# notch.net
KiCad netlist of a schematic drawn in EAGLE
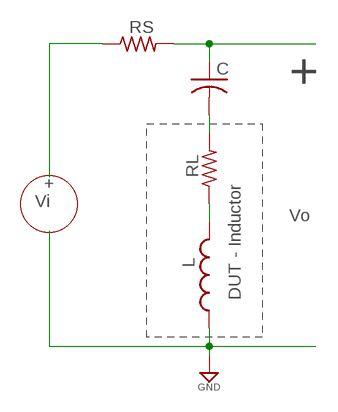
[diagram p0: schematic, sheet 1]

(export (version "E")
  (design (tool "Eeschema 10.0.6"))
  (components
    (comp (ref "C")
      (value "C-US050-030X075")
      (footprint "eagle-import:C050-030X075")
      (libsource (lib "eagle-import") (part "C-US050-030X075"))
    )
    (comp (ref "L")
      (value "L-USL0201")
      (footprint "eagle-import:L0201")
      (libsource (lib "eagle-import") (part "L-USL0201"))
    )
    (comp (ref "RL")
      (value "R-US_0411/15")
      (footprint "eagle-import:0411_15")
      (libsource (lib "eagle-import") (part "R-US_0411/15"))
    )
    (comp (ref "RS")
      (value "R-US_0411/15")
      (footprint "eagle-import:0411_15")
      (libsource (lib "eagle-import") (part "R-US_0411/15"))
    )
  )
  (nets
    (net (code "1") (name "GND") (class "Default")
      (node (ref "L") (pin "1") (pinfunction "1_1") (pintype "passive"))
    )
    (net (code "2") (name "Net-(C-Pad1)") (class "Default")
      (node (ref "C") (pin "1") (pinfunction "1_1") (pintype "passive"))
      (node (ref "RS") (pin "2") (pinfunction "2_2") (pintype "passive"))
    )
    (net (code "3") (name "Net-(C-Pad2)") (class "Default")
      (node (ref "C") (pin "2") (pinfunction "2_2") (pintype "passive"))
      (node (ref "RL") (pin "2") (pinfunction "2_2") (pintype "passive"))
    )
    (net (code "4") (name "Net-(L-Pad2)") (class "Default")
      (node (ref "L") (pin "2") (pinfunction "2_2") (pintype "passive"))
      (node (ref "RL") (pin "1") (pinfunction "1_1") (pintype "passive"))
    )
    (net (code "5") (name "unconnected-(RS-Pad1)") (class "Default")
      (node (ref "RS") (pin "1") (pinfunction "1_1") (pintype "passive"))
    )
  )
)
